# SCH_usb_12v_ups_v0_1_2023-01-08.net
KiCad netlist of a schematic drawn in EasyEDA
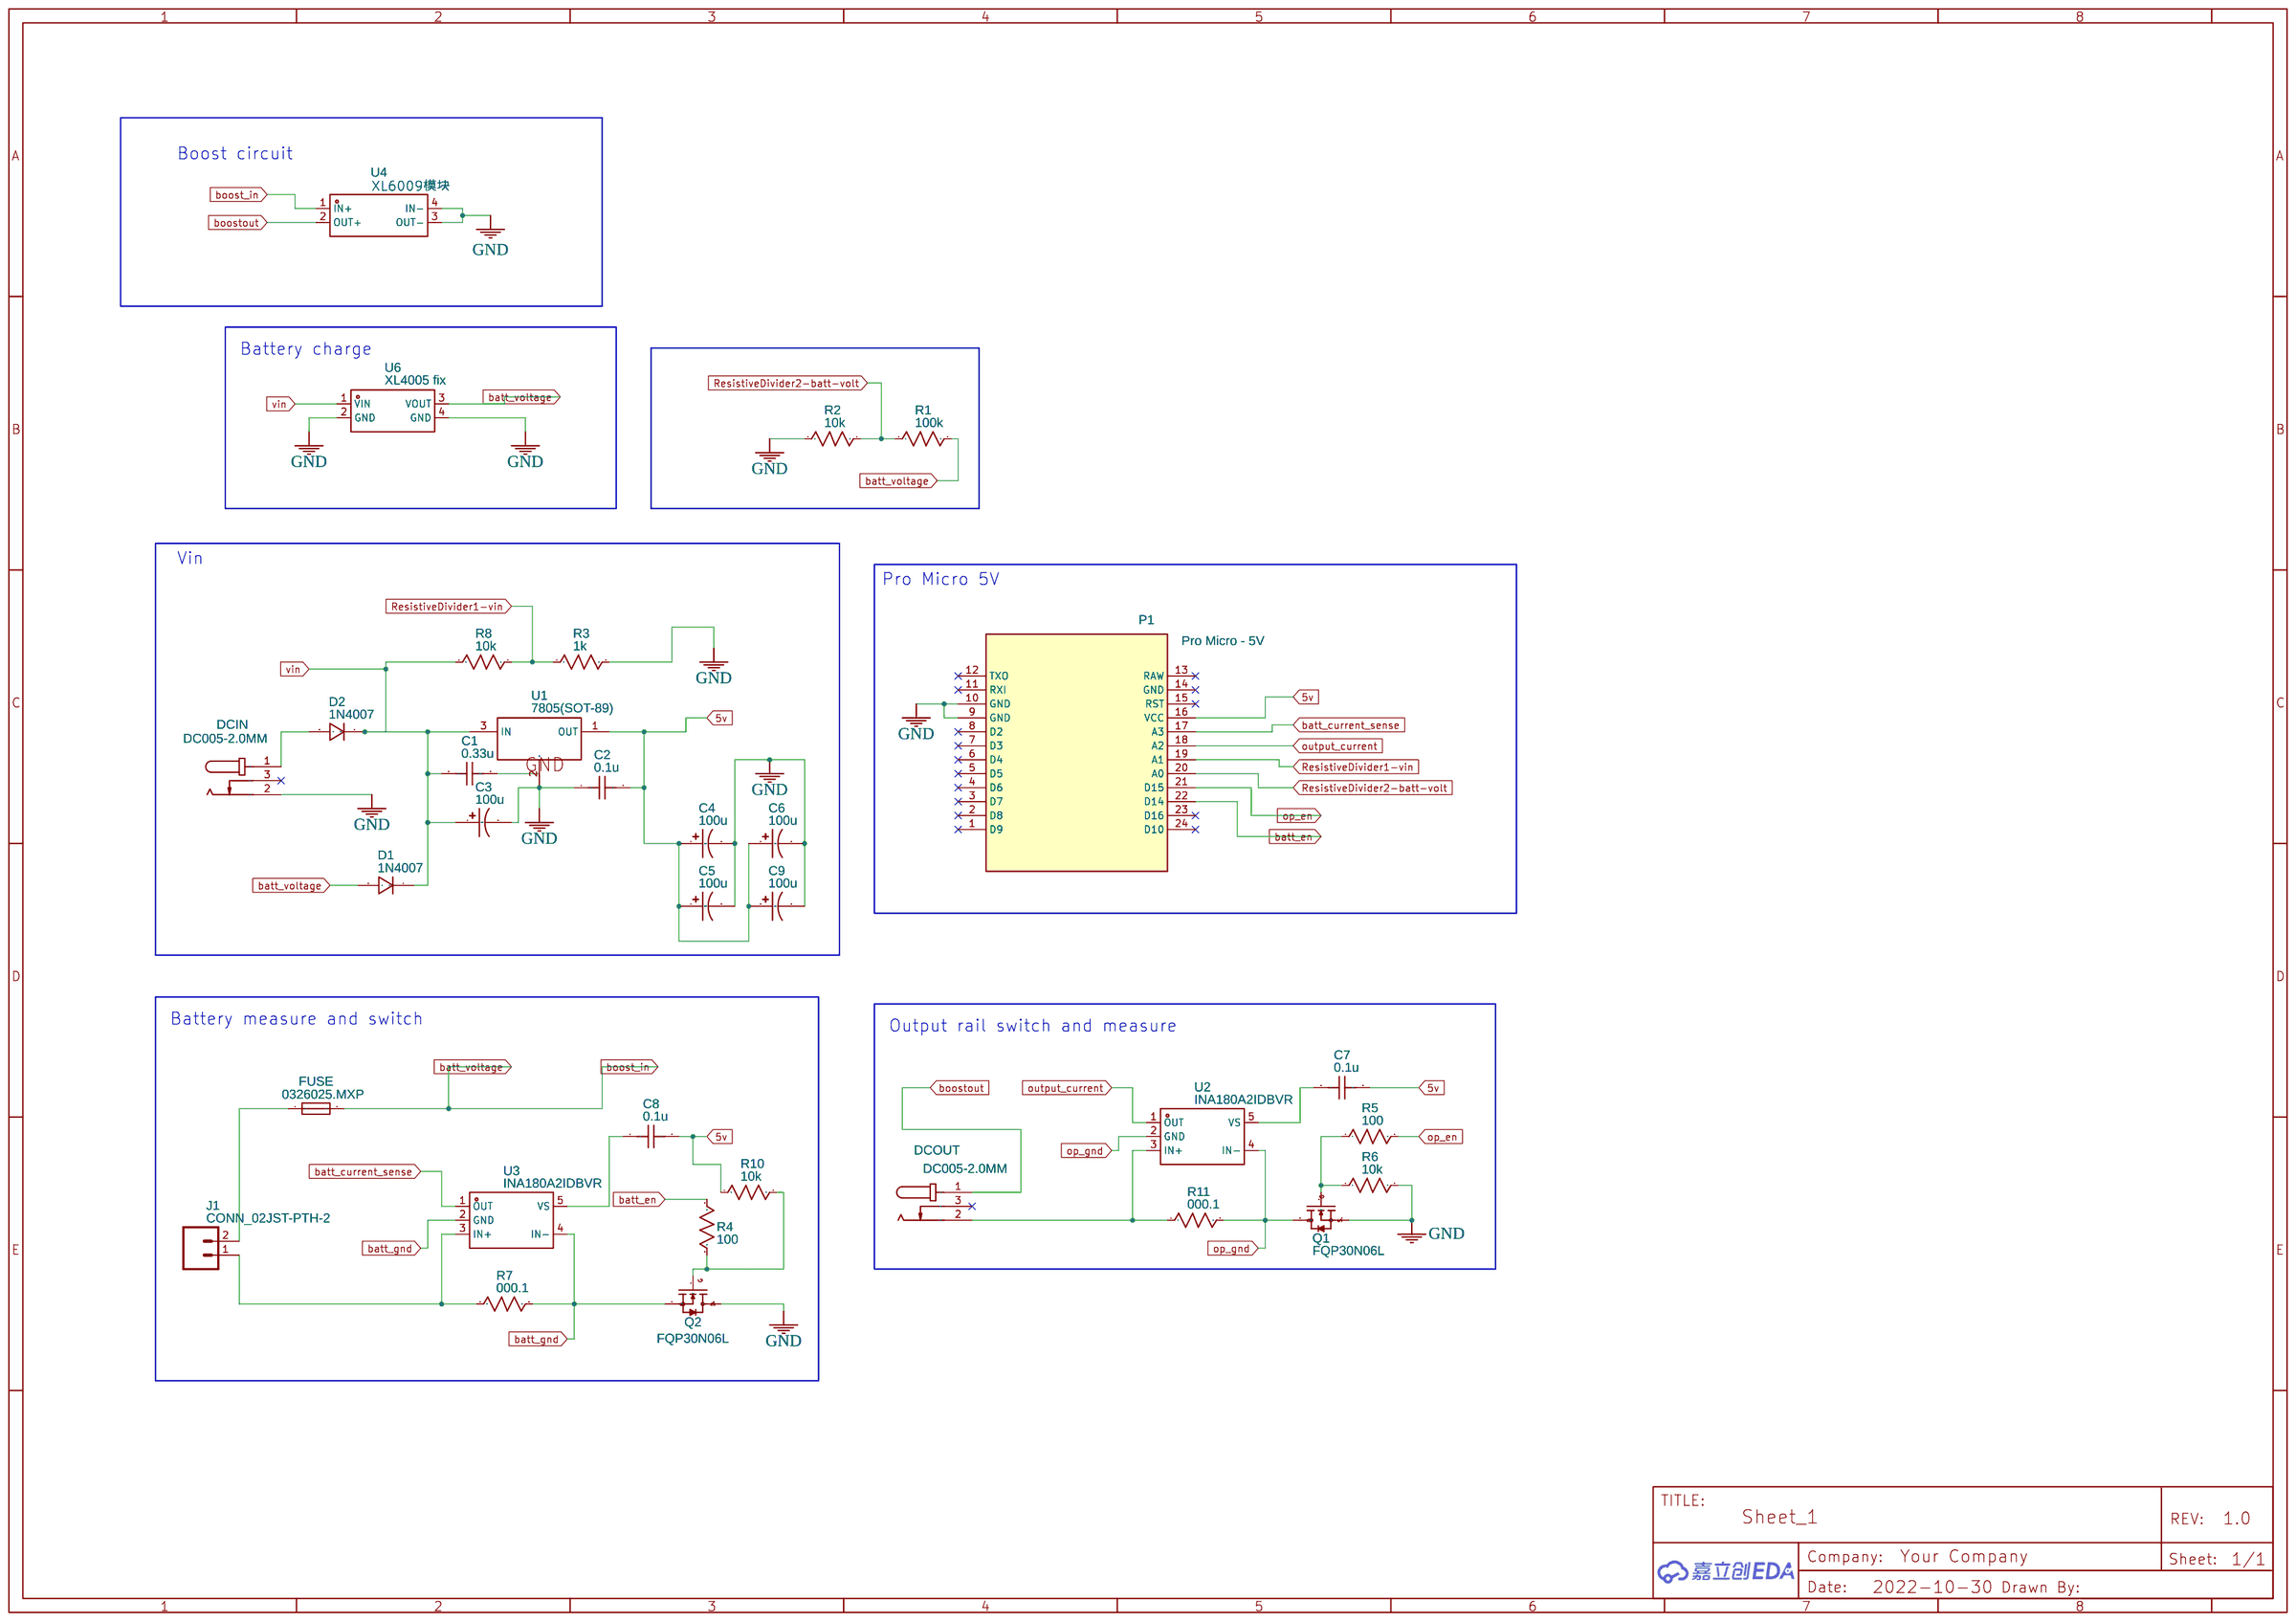
[diagram p0: schematic sheet]

(export (version "E")
  (design (tool "Eeschema 10.0.6"))
  (components
    (comp (ref "C1") (value "0.33u") (libsource (lib "") (part "C_0603_US")))
    (comp (ref "C2") (value "0.1u") (libsource (lib "") (part "C_0603_US")))
    (comp (ref "C3") (value "100u") (libsource (lib "") (part "CE_TH_D6.3×F2.5_US")))
    (comp (ref "C4") (value "100u") (libsource (lib "") (part "CE_TH_D6.3×F2.5_US")))
    (comp (ref "C5") (value "100u") (libsource (lib "") (part "CE_TH_D6.3×F2.5_US")))
    (comp (ref "C6") (value "100u") (libsource (lib "") (part "CE_TH_D6.3×F2.5_US")))
    (comp (ref "C7") (value "0.1u") (libsource (lib "") (part "C_RAD-0.1_US")))
    (comp (ref "C8") (value "0.1u") (libsource (lib "") (part "C_RAD-0.1_US")))
    (comp (ref "C9") (value "100u") (libsource (lib "") (part "CE_TH_D6.3×F2.5_US")))
    (comp (ref "D1")
      (value "1N4007")
      (fields (field (name "BOM_Supplier Part") "C106903"))
      (libsource (lib "") (part "1N4007"))
    )
    (comp (ref "D2")
      (value "1N4007")
      (fields (field (name "BOM_Supplier Part") "C106903"))
      (libsource (lib "") (part "1N4007"))
    )
    (comp (ref "DCIN")
      (value "DC005-2.0MM")
      (fields (field (name "BOM_Supplier Part") "C111567"))
      (libsource (lib "") (part "DC005-2.0MM_1"))
    )
    (comp (ref "DCOUT")
      (value "DC005-2.0MM")
      (fields (field (name "BOM_Supplier Part") "C111567"))
      (libsource (lib "") (part "DC005-2.0MM"))
    )
    (comp (ref "FUSE")
      (value "0326025.MXP")
      (fields (field (name "BOM_Supplier Part") "C178977"))
      (libsource (lib "") (part "0326025.MXP"))
    )
    (comp (ref "J1") (value "CONN_02JST-PTH-2") (libsource (lib "") (part "CONN_02JST-PTH-2")))
    (comp (ref "P1") (value "Pro Micro - 5V") (libsource (lib "") (part "Pro Micro - 5V")))
    (comp (ref "Q1") (value "FQP30N06L") (libsource (lib "") (part "FQP30N06L")))
    (comp (ref "Q2") (value "FQP30N06L") (libsource (lib "") (part "FQP30N06L_1")))
    (comp (ref "R1") (value "100k") (libsource (lib "") (part "R_1210_US")))
    (comp (ref "R2") (value "10k") (libsource (lib "") (part "R_1210_US")))
    (comp (ref "R3") (value "1k") (libsource (lib "") (part "R_1210_US")))
    (comp (ref "R4") (value "100") (libsource (lib "") (part "R_1210_US_1")))
    (comp (ref "R5") (value "100") (libsource (lib "") (part "R_1210_US")))
    (comp (ref "R6") (value "10k") (libsource (lib "") (part "R_1210_US")))
    (comp (ref "R7") (value "000.1") (libsource (lib "") (part "R_AXIAL-1.0_US")))
    (comp (ref "R8") (value "10k") (libsource (lib "") (part "R_1210_US")))
    (comp (ref "R10") (value "10k") (libsource (lib "") (part "R_1210_US")))
    (comp (ref "R11") (value "000.1") (libsource (lib "") (part "R_AXIAL-1.0_US")))
    (comp (ref "U1")
      (value "7805(SOT-89)")
      (fields (field (name "BOM_Manufacturer Part") "CJ78L05") (field (name "BOM_Supplier Part") "C2079"))
      (libsource (lib "") (part "7805(SOT-89)"))
    )
    (comp (ref "U2")
      (value "INA180A2IDBVR")
      (fields (field (name "BOM_Supplier Part") "C192764"))
      (libsource (lib "") (part "INA180A2IDBVR"))
    )
    (comp (ref "U3")
      (value "INA180A2IDBVR")
      (fields (field (name "BOM_Supplier Part") "C192764"))
      (libsource (lib "") (part "INA180A2IDBVR"))
    )
    (comp (ref "U4")
      (value "XL6009模块")
      (fields (field (name "BOM_Manufacturer Part") "xl6009模块") (field (name "BOM_Supplier Part") "C2908146"))
      (libsource (lib "") (part "XL6009模块"))
    )
    (comp (ref "U6") (value "XL4005 fix") (libsource (lib "") (part "XL4005 fix")))
  )
  (nets
    (net (code "1") (name "5v") (class "Default")
      (node (ref "C2") (pin "2") (pinfunction "2_2") (pintype "unspecified"))
      (node (ref "C4") (pin "1") (pinfunction "1_1") (pintype "unspecified"))
      (node (ref "C5") (pin "1") (pinfunction "1_1") (pintype "unspecified"))
      (node (ref "C6") (pin "1") (pinfunction "1_1") (pintype "unspecified"))
      (node (ref "C7") (pin "2") (pinfunction "2_2") (pintype "unspecified"))
      (node (ref "C8") (pin "2") (pinfunction "2_2") (pintype "unspecified"))
      (node (ref "C9") (pin "1") (pinfunction "1_1") (pintype "unspecified"))
      (node (ref "P1") (pin "16") (pinfunction "VCC_16") (pintype "unspecified"))
      (node (ref "R10") (pin "1") (pinfunction "1_1") (pintype "unspecified"))
      (node (ref "U1") (pin "1") (pinfunction "OUT_1") (pintype "passive"))
    )
    (net (code "2") (name "GND") (class "Default")
      (node (ref "C1") (pin "2") (pinfunction "2_2") (pintype "unspecified"))
      (node (ref "C2") (pin "1") (pinfunction "1_1") (pintype "unspecified"))
      (node (ref "C3") (pin "2") (pinfunction "2_2") (pintype "unspecified"))
      (node (ref "C4") (pin "2") (pinfunction "2_2") (pintype "unspecified"))
      (node (ref "C5") (pin "2") (pinfunction "2_2") (pintype "unspecified"))
      (node (ref "C6") (pin "2") (pinfunction "2_2") (pintype "unspecified"))
      (node (ref "C9") (pin "2") (pinfunction "2_2") (pintype "unspecified"))
      (node (ref "DCIN") (pin "2") (pinfunction "2_2") (pintype "unspecified"))
      (node (ref "P1") (pin "10") (pinfunction "GND_10") (pintype "unspecified"))
      (node (ref "P1") (pin "9") (pinfunction "GND_9") (pintype "unspecified"))
      (node (ref "Q1") (pin "3") (pinfunction "S_3") (pintype "unspecified"))
      (node (ref "Q2") (pin "2") (pinfunction "D_2") (pintype "unspecified"))
      (node (ref "R2") (pin "1") (pinfunction "1_1") (pintype "unspecified"))
      (node (ref "R3") (pin "2") (pinfunction "2_2") (pintype "unspecified"))
      (node (ref "R6") (pin "2") (pinfunction "2_2") (pintype "unspecified"))
      (node (ref "U1") (pin "2") (pinfunction "GND_2") (pintype "passive"))
      (node (ref "U4") (pin "3") (pinfunction "OUT-_3") (pintype "unspecified"))
      (node (ref "U4") (pin "4") (pinfunction "IN-_4") (pintype "unspecified"))
      (node (ref "U6") (pin "2") (pinfunction "GND_2") (pintype "unspecified"))
      (node (ref "U6") (pin "4") (pinfunction "GND_4") (pintype "unspecified"))
    )
    (net (code "3") (name "Net-(D2-Pad2)") (class "Default")
      (node (ref "D2") (pin "2") (pinfunction "2_2") (pintype "unspecified"))
      (node (ref "DCIN") (pin "1") (pinfunction "1_1") (pintype "unspecified"))
    )
    (net (code "4") (name "Net-(FUSE-Pad1)") (class "Default")
      (node (ref "FUSE") (pin "1") (pinfunction "1_1") (pintype "unspecified"))
      (node (ref "J1") (pin "2") (pinfunction "2_2") (pintype "bidirectional"))
    )
    (net (code "5") (name "Net-(Q1-G)") (class "Default")
      (node (ref "Q1") (pin "1") (pinfunction "G_1") (pintype "unspecified"))
      (node (ref "R5") (pin "1") (pinfunction "1_1") (pintype "unspecified"))
      (node (ref "R6") (pin "1") (pinfunction "1_1") (pintype "unspecified"))
    )
    (net (code "6") (name "Net-(Q2-G)") (class "Default")
      (node (ref "Q2") (pin "1") (pinfunction "G_1") (pintype "unspecified"))
      (node (ref "R10") (pin "2") (pinfunction "2_2") (pintype "unspecified"))
      (node (ref "R4") (pin "2") (pinfunction "2_2") (pintype "unspecified"))
    )
    (net (code "7") (name "Net-(U2-IN+)") (class "Default")
      (node (ref "DCOUT") (pin "2") (pinfunction "2_2") (pintype "unspecified"))
      (node (ref "R11") (pin "1") (pinfunction "1_1") (pintype "unspecified"))
      (node (ref "U2") (pin "3") (pinfunction "IN+_3") (pintype "unspecified"))
    )
    (net (code "8") (name "Net-(U2-VS)") (class "Default")
      (node (ref "C7") (pin "1") (pinfunction "1_1") (pintype "unspecified"))
      (node (ref "U2") (pin "5") (pinfunction "VS_5") (pintype "unspecified"))
    )
    (net (code "9") (name "Net-(U3-IN+)") (class "Default")
      (node (ref "J1") (pin "1") (pinfunction "1_1") (pintype "bidirectional"))
      (node (ref "R7") (pin "1") (pinfunction "1_1") (pintype "unspecified"))
      (node (ref "U3") (pin "3") (pinfunction "IN+_3") (pintype "unspecified"))
    )
    (net (code "10") (name "Net-(U3-VS)") (class "Default")
      (node (ref "C8") (pin "1") (pinfunction "1_1") (pintype "unspecified"))
      (node (ref "U3") (pin "5") (pinfunction "VS_5") (pintype "unspecified"))
    )
    (net (code "11") (name "ResistiveDivider1-vin") (class "Default")
      (node (ref "P1") (pin "19") (pinfunction "A1_19") (pintype "unspecified"))
      (node (ref "R3") (pin "1") (pinfunction "1_1") (pintype "unspecified"))
      (node (ref "R8") (pin "2") (pinfunction "2_2") (pintype "unspecified"))
    )
    (net (code "12") (name "ResistiveDivider2-batt-volt") (class "Default")
      (node (ref "P1") (pin "20") (pinfunction "A0_20") (pintype "unspecified"))
      (node (ref "R1") (pin "1") (pinfunction "1_1") (pintype "unspecified"))
      (node (ref "R2") (pin "2") (pinfunction "2_2") (pintype "unspecified"))
    )
    (net (code "13") (name "batt_current_sense") (class "Default")
      (node (ref "P1") (pin "17") (pinfunction "A3_17") (pintype "unspecified"))
      (node (ref "U3") (pin "1") (pinfunction "OUT_1") (pintype "unspecified"))
    )
    (net (code "14") (name "batt_en") (class "Default")
      (node (ref "P1") (pin "22") (pinfunction "D14_22") (pintype "unspecified"))
      (node (ref "R4") (pin "1") (pinfunction "1_1") (pintype "unspecified"))
    )
    (net (code "15") (name "batt_gnd") (class "Default")
      (node (ref "Q2") (pin "3") (pinfunction "S_3") (pintype "unspecified"))
      (node (ref "R7") (pin "2") (pinfunction "2_2") (pintype "unspecified"))
      (node (ref "U3") (pin "2") (pinfunction "GND_2") (pintype "unspecified"))
      (node (ref "U3") (pin "4") (pinfunction "IN-_4") (pintype "unspecified"))
    )
    (net (code "16") (name "batt_voltage") (class "Default")
      (node (ref "D1") (pin "2") (pinfunction "2_2") (pintype "unspecified"))
      (node (ref "FUSE") (pin "2") (pinfunction "2_2") (pintype "unspecified"))
      (node (ref "R1") (pin "2") (pinfunction "2_2") (pintype "unspecified"))
      (node (ref "U4") (pin "1") (pinfunction "IN+_1") (pintype "unspecified"))
      (node (ref "U6") (pin "3") (pinfunction "VOUT_3") (pintype "unspecified"))
    )
    (net (code "17") (name "boostout") (class "Default")
      (node (ref "DCOUT") (pin "1") (pinfunction "1_1") (pintype "unspecified"))
      (node (ref "U4") (pin "2") (pinfunction "OUT+_2") (pintype "unspecified"))
    )
    (net (code "18") (name "op_en") (class "Default")
      (node (ref "P1") (pin "21") (pinfunction "D15_21") (pintype "unspecified"))
      (node (ref "R5") (pin "2") (pinfunction "2_2") (pintype "unspecified"))
    )
    (net (code "19") (name "op_gnd") (class "Default")
      (node (ref "Q1") (pin "2") (pinfunction "D_2") (pintype "unspecified"))
      (node (ref "R11") (pin "2") (pinfunction "2_2") (pintype "unspecified"))
      (node (ref "U2") (pin "2") (pinfunction "GND_2") (pintype "unspecified"))
      (node (ref "U2") (pin "4") (pinfunction "IN-_4") (pintype "unspecified"))
    )
    (net (code "20") (name "output_current") (class "Default")
      (node (ref "P1") (pin "18") (pinfunction "A2_18") (pintype "unspecified"))
      (node (ref "U2") (pin "1") (pinfunction "OUT_1") (pintype "unspecified"))
    )
    (net (code "21") (name "unconnected-(DCIN-Pad3)") (class "Default")
      (node (ref "DCIN") (pin "3") (pinfunction "3_3") (pintype "unspecified+no_connect"))
    )
    (net (code "22") (name "unconnected-(DCOUT-Pad3)") (class "Default")
      (node (ref "DCOUT") (pin "3") (pinfunction "3_3") (pintype "unspecified+no_connect"))
    )
    (net (code "23") (name "unconnected-(P1-D2-Pad8)") (class "Default")
      (node (ref "P1") (pin "8") (pinfunction "D2_8") (pintype "unspecified+no_connect"))
    )
    (net (code "24") (name "unconnected-(P1-D3-Pad7)") (class "Default")
      (node (ref "P1") (pin "7") (pinfunction "D3_7") (pintype "unspecified+no_connect"))
    )
    (net (code "25") (name "unconnected-(P1-D4-Pad6)") (class "Default")
      (node (ref "P1") (pin "6") (pinfunction "D4_6") (pintype "unspecified+no_connect"))
    )
    (net (code "26") (name "unconnected-(P1-D5-Pad5)") (class "Default")
      (node (ref "P1") (pin "5") (pinfunction "D5_5") (pintype "unspecified+no_connect"))
    )
    (net (code "27") (name "unconnected-(P1-D6-Pad4)") (class "Default")
      (node (ref "P1") (pin "4") (pinfunction "D6_4") (pintype "unspecified+no_connect"))
    )
    (net (code "28") (name "unconnected-(P1-D7-Pad3)") (class "Default")
      (node (ref "P1") (pin "3") (pinfunction "D7_3") (pintype "unspecified+no_connect"))
    )
    (net (code "29") (name "unconnected-(P1-D8-Pad2)") (class "Default")
      (node (ref "P1") (pin "2") (pinfunction "D8_2") (pintype "unspecified+no_connect"))
    )
    (net (code "30") (name "unconnected-(P1-D9-Pad1)") (class "Default")
      (node (ref "P1") (pin "1") (pinfunction "D9_1") (pintype "unspecified+no_connect"))
    )
    (net (code "31") (name "unconnected-(P1-D10-Pad24)") (class "Default")
      (node (ref "P1") (pin "24") (pinfunction "D10_24") (pintype "unspecified+no_connect"))
    )
    (net (code "32") (name "unconnected-(P1-D16-Pad23)") (class "Default")
      (node (ref "P1") (pin "23") (pinfunction "D16_23") (pintype "unspecified+no_connect"))
    )
    (net (code "33") (name "unconnected-(P1-GND-Pad14)") (class "Default")
      (node (ref "P1") (pin "14") (pinfunction "GND_14") (pintype "unspecified+no_connect"))
    )
    (net (code "34") (name "unconnected-(P1-RAW-Pad13)") (class "Default")
      (node (ref "P1") (pin "13") (pinfunction "RAW_13") (pintype "unspecified+no_connect"))
    )
    (net (code "35") (name "unconnected-(P1-RST-Pad15)") (class "Default")
      (node (ref "P1") (pin "15") (pinfunction "RST_15") (pintype "unspecified+no_connect"))
    )
    (net (code "36") (name "unconnected-(P1-RXI-Pad11)") (class "Default")
      (node (ref "P1") (pin "11") (pinfunction "RXI_11") (pintype "unspecified+no_connect"))
    )
    (net (code "37") (name "unconnected-(P1-TXO-Pad12)") (class "Default")
      (node (ref "P1") (pin "12") (pinfunction "TXO_12") (pintype "unspecified+no_connect"))
    )
    (net (code "38") (name "vin") (class "Default")
      (node (ref "C1") (pin "1") (pinfunction "1_1") (pintype "unspecified"))
      (node (ref "C3") (pin "1") (pinfunction "1_1") (pintype "unspecified"))
      (node (ref "D1") (pin "1") (pinfunction "1_1") (pintype "unspecified"))
      (node (ref "D2") (pin "1") (pinfunction "1_1") (pintype "unspecified"))
      (node (ref "R8") (pin "1") (pinfunction "1_1") (pintype "unspecified"))
      (node (ref "U1") (pin "3") (pinfunction "IN_3") (pintype "passive"))
      (node (ref "U6") (pin "1") (pinfunction "VIN_1") (pintype "unspecified"))
    )
  )
)
